# USB.net
KiCad netlist of a schematic drawn in EAGLE
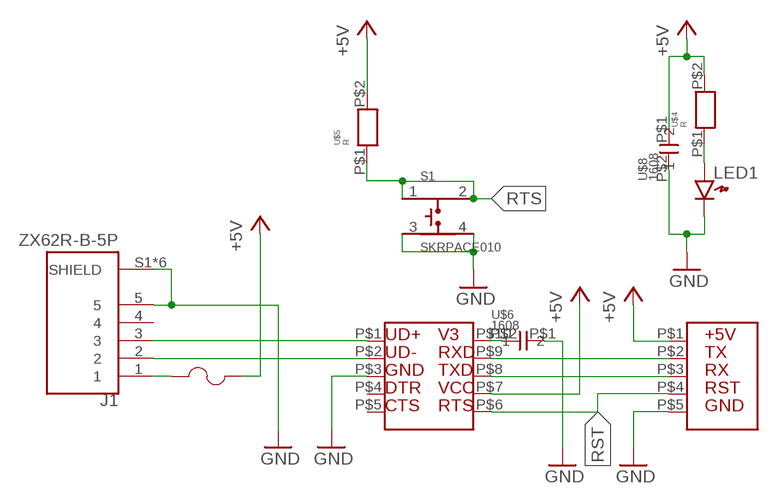
[diagram p0: schematic, sheet 1]

(export (version "E")
  (design (tool "Eeschema 10.0.6"))
  (components
    (comp (ref "J1")
      (value "ZX62R-B-5P")
      (footprint "eagle-import:HRS_ZX62R-B-5P")
      (fields (field (name "MF") "Hirose"))
      (libsource (lib "eagle-import") (part "ZX62R-B-5P"))
    )
    (comp (ref "LED1")
      (value "LED1608")
      (footprint "eagle-import:LED1608")
      (libsource (lib "eagle-import") (part "LED1608"))
    )
    (comp (ref "S1")
      (value "SKRPACE010")
      (footprint "eagle-import:SW_SKRPACE010")
      (fields (field (name "MF") "ALPS"))
      (libsource (lib "eagle-import") (part "SKRPACE010"))
    )
    (comp (ref "U$1")
      (value "CH340K")
      (footprint "eagle-import:CH340K")
      (libsource (lib "eagle-import") (part "CH340K"))
    )
    (comp (ref "U$2") (value "F") (footprint "eagle-import:F") (libsource (lib "eagle-import") (part "F")))
    (comp (ref "U$3") (value "SI") (footprint "eagle-import:SI") (libsource (lib "eagle-import") (part "SI")))
    (comp (ref "U$4") (value "R") (footprint "eagle-import:1608") (libsource (lib "eagle-import") (part "R")))
    (comp (ref "U$5") (value "R") (footprint "eagle-import:1608") (libsource (lib "eagle-import") (part "R")))
    (comp (ref "U$6")
      (value "1608")
      (footprint "eagle-import:CON")
      (libsource (lib "eagle-import") (part "1608"))
    )
    (comp (ref "U$8")
      (value "1608")
      (footprint "eagle-import:CON")
      (libsource (lib "eagle-import") (part "1608"))
    )
  )
  (nets
    (net (code "1") (name "+5V") (class "Default")
      (node (ref "U$1") (pin "P$7") (pinfunction "P$7_P$7") (pintype "bidirectional"))
      (node (ref "U$2") (pin "P$1") (pinfunction "P$1_P$1") (pintype "bidirectional"))
      (node (ref "U$3") (pin "P$1") (pinfunction "P$1_P$1") (pintype "bidirectional"))
      (node (ref "U$4") (pin "P$2") (pinfunction "P$2_P$2") (pintype "bidirectional"))
      (node (ref "U$5") (pin "P$2") (pinfunction "P$2_P$2") (pintype "bidirectional"))
      (node (ref "U$8") (pin "P$1") (pinfunction "1_P$1") (pintype "bidirectional"))
    )
    (net (code "2") (name "GND") (class "Default")
      (node (ref "J1") (pin "5") (pinfunction "5_5") (pintype "passive"))
      (node (ref "J1") (pin "S1") (pinfunction "SHIELD_S1") (pintype "passive"))
      (node (ref "J1") (pin "S2") (pinfunction "SHIELD_S2") (pintype "passive"))
      (node (ref "J1") (pin "S3") (pinfunction "SHIELD_S3") (pintype "passive"))
      (node (ref "J1") (pin "S4") (pinfunction "SHIELD_S4") (pintype "passive"))
      (node (ref "J1") (pin "S5") (pinfunction "SHIELD_S5") (pintype "passive"))
      (node (ref "J1") (pin "S6") (pinfunction "SHIELD_S6") (pintype "passive"))
      (node (ref "LED1") (pin "K") (pinfunction "K_K") (pintype "passive"))
      (node (ref "S1") (pin "3") (pinfunction "3_3") (pintype "bidirectional"))
      (node (ref "S1") (pin "4") (pinfunction "4_4") (pintype "bidirectional"))
      (node (ref "U$1") (pin "P$3") (pinfunction "P$3_P$3") (pintype "bidirectional"))
      (node (ref "U$3") (pin "P$5") (pinfunction "P$5_P$5") (pintype "bidirectional"))
      (node (ref "U$6") (pin "P$1") (pinfunction "1_P$1") (pintype "bidirectional"))
      (node (ref "U$8") (pin "P$2") (pinfunction "2_P$2") (pintype "bidirectional"))
    )
    (net (code "3") (name "Net-(J1-Pad1)") (class "Default")
      (node (ref "J1") (pin "1") (pinfunction "1_1") (pintype "passive"))
      (node (ref "U$2") (pin "P$2") (pinfunction "P$2_P$2") (pintype "bidirectional"))
    )
    (net (code "4") (name "Net-(J1-Pad2)") (class "Default")
      (node (ref "J1") (pin "2") (pinfunction "2_2") (pintype "passive"))
      (node (ref "U$1") (pin "P$2") (pinfunction "P$2_P$2") (pintype "bidirectional"))
    )
    (net (code "5") (name "Net-(J1-Pad3)") (class "Default")
      (node (ref "J1") (pin "3") (pinfunction "3_3") (pintype "passive"))
      (node (ref "U$1") (pin "P$1") (pinfunction "P$1_P$1") (pintype "bidirectional"))
    )
    (net (code "6") (name "Net-(LED1-PadA)") (class "Default")
      (node (ref "LED1") (pin "A") (pinfunction "A_A") (pintype "passive"))
      (node (ref "U$4") (pin "P$1") (pinfunction "P$1_P$1") (pintype "bidirectional"))
    )
    (net (code "7") (name "Net-(U$1-PadP$8)") (class "Default")
      (node (ref "U$1") (pin "P$8") (pinfunction "P$8_P$8") (pintype "bidirectional"))
      (node (ref "U$3") (pin "P$3") (pinfunction "P$3_P$3") (pintype "bidirectional"))
    )
    (net (code "8") (name "Net-(U$1-PadP$9)") (class "Default")
      (node (ref "U$1") (pin "P$9") (pinfunction "P$9_P$9") (pintype "bidirectional"))
      (node (ref "U$3") (pin "P$2") (pinfunction "P$2_P$2") (pintype "bidirectional"))
    )
    (net (code "9") (name "Net-(U$6-2)") (class "Default")
      (node (ref "U$1") (pin "P$10") (pinfunction "P$10_P$10") (pintype "bidirectional"))
      (node (ref "U$6") (pin "P$2") (pinfunction "2_P$2") (pintype "bidirectional"))
    )
    (net (code "10") (name "RST") (class "Default")
      (node (ref "U$1") (pin "P$6") (pinfunction "P$6_P$6") (pintype "bidirectional"))
      (node (ref "U$3") (pin "P$4") (pinfunction "P$4_P$4") (pintype "bidirectional"))
    )
    (net (code "11") (name "RTS") (class "Default")
      (node (ref "S1") (pin "1") (pinfunction "1_1") (pintype "bidirectional"))
      (node (ref "S1") (pin "2") (pinfunction "2_2") (pintype "bidirectional"))
      (node (ref "U$5") (pin "P$1") (pinfunction "P$1_P$1") (pintype "bidirectional"))
    )
    (net (code "12") (name "unconnected-(J1-Pad4)") (class "Default")
      (node (ref "J1") (pin "4") (pinfunction "4_4") (pintype "passive"))
    )
    (net (code "13") (name "unconnected-(U$1-PadP$4)") (class "Default")
      (node (ref "U$1") (pin "P$4") (pinfunction "P$4_P$4") (pintype "bidirectional"))
    )
    (net (code "14") (name "unconnected-(U$1-PadP$5)") (class "Default")
      (node (ref "U$1") (pin "P$5") (pinfunction "P$5_P$5") (pintype "bidirectional"))
    )
  )
)
